# Board.net
KiCad netlist of a schematic drawn in EAGLE
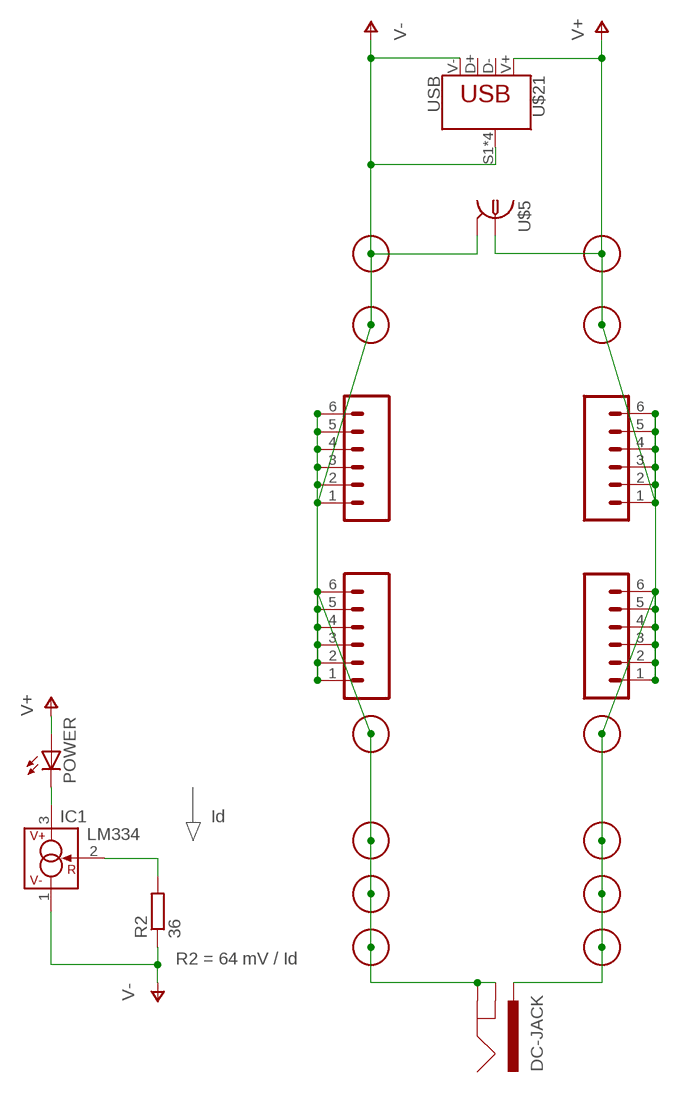
[diagram p0: schematic, sheet 1]

(export (version "E")
  (design (tool "Eeschema 10.0.6"))
  (components
    (comp (ref "IC1")
      (value "LM334")
      (footprint "eagle-import:SO08")
      (libsource (lib "eagle-import") (part "LM34SM3"))
    )
    (comp (ref "POWER")
      (value "LED5MM")
      (footprint "eagle-import:LED5MM")
      (libsource (lib "eagle-import") (part "LED5MM"))
    )
    (comp (ref "R2")
      (value "36")
      (footprint "eagle-import:R0603")
      (libsource (lib "eagle-import") (part "R-EU_R0603"))
    )
    (comp (ref "U$1")
      (value "6MM-BANANA-PLUGSCREW-BLACK")
      (footprint "eagle-import:6MM-TERMINAL-POST-BLACK")
      (libsource (lib "eagle-import") (part "6MM-BANANA-PLUGSCREW-BLACK"))
    )
    (comp (ref "U$2")
      (value "6MM-BANANA-PLUGSCREW-RED")
      (footprint "eagle-import:6MM-TERMINAL-POST-RED")
      (libsource (lib "eagle-import") (part "6MM-BANANA-PLUGSCREW-RED"))
    )
    (comp (ref "U$3")
      (value "6MM-BANANA-PLUGSCREW-BLACK")
      (footprint "eagle-import:6MM-TERMINAL-POST-BLACK")
      (libsource (lib "eagle-import") (part "6MM-BANANA-PLUGSCREW-BLACK"))
    )
    (comp (ref "U$4")
      (value "6MM-BANANA-PLUGSCREW-RED")
      (footprint "eagle-import:6MM-TERMINAL-POST-RED")
      (libsource (lib "eagle-import") (part "6MM-BANANA-PLUGSCREW-RED"))
    )
    (comp (ref "U$5")
      (value "BNC-VTE-1-1337541-0")
      (footprint "eagle-import:BNC-V")
      (libsource (lib "eagle-import") (part "BNC-VTE-1-1337541-0"))
    )
    (comp (ref "U$6")
      (value "PINHEADER-1X6MALE_LOCK")
      (footprint "eagle-import:1X06_LOCK")
      (libsource (lib "eagle-import") (part "PINHEADER-1X6MALE_LOCK"))
    )
    (comp (ref "U$7")
      (value "PINHEADER-1X6MALE_LOCK")
      (footprint "eagle-import:1X06_LOCK")
      (libsource (lib "eagle-import") (part "PINHEADER-1X6MALE_LOCK"))
    )
    (comp (ref "U$8")
      (value "PINHEADER-1X6FEMALE_LOCK")
      (footprint "eagle-import:1X06_FEMALE_LOCK.010")
      (libsource (lib "eagle-import") (part "PINHEADER-1X6FEMALE_LOCK"))
    )
    (comp (ref "U$9")
      (value "PINHEADER-1X6FEMALE_LOCK")
      (footprint "eagle-import:1X06_FEMALE_LOCK.010")
      (libsource (lib "eagle-import") (part "PINHEADER-1X6FEMALE_LOCK"))
    )
    (comp (ref "U$10")
      (value "TERMINAL-BLOCK-2")
      (footprint "eagle-import:MKDSN1,5_2-5,08")
      (libsource (lib "eagle-import") (part "TERMINAL-BLOCK-2"))
    )
    (comp (ref "U$12")
      (value "DC-JACK")
      (footprint "eagle-import:POWER_JACK_PTH")
      (libsource (lib "eagle-import") (part "DC-JACK"))
    )
    (comp (ref "U$14")
      (value "TERMINAL-1")
      (footprint "eagle-import:TE-726386")
      (libsource (lib "eagle-import") (part "TERMINAL-1"))
    )
    (comp (ref "U$15")
      (value "TERMINAL-1")
      (footprint "eagle-import:TE-726386")
      (libsource (lib "eagle-import") (part "TERMINAL-1"))
    )
    (comp (ref "U$16")
      (value "TERMINAL-1BRIDGE")
      (footprint "eagle-import:VOGT-1098A.68")
      (libsource (lib "eagle-import") (part "TERMINAL-1BRIDGE"))
    )
    (comp (ref "U$17")
      (value "TERMINAL-1BRIDGE")
      (footprint "eagle-import:VOGT-1098A.68")
      (libsource (lib "eagle-import") (part "TERMINAL-1BRIDGE"))
    )
    (comp (ref "U$18")
      (value "TERMINAL-1")
      (footprint "eagle-import:TE-726386")
      (libsource (lib "eagle-import") (part "TERMINAL-1"))
    )
    (comp (ref "U$19")
      (value "TERMINAL-1")
      (footprint "eagle-import:TE-726386")
      (libsource (lib "eagle-import") (part "TERMINAL-1"))
    )
    (comp (ref "U$21")
      (value "USB")
      (footprint "eagle-import:ECON-USBBUVA")
      (libsource (lib "eagle-import") (part "USB"))
    )
  )
  (nets
    (net (code "1") (name "Net-(IC1-R)") (class "Default")
      (node (ref "IC1") (pin "2") (pinfunction "R_2") (pintype "passive"))
      (node (ref "R2") (pin "2") (pinfunction "2_2") (pintype "passive"))
    )
    (net (code "2") (name "Net-(IC1-V+)") (class "Default")
      (node (ref "IC1") (pin "3") (pinfunction "V+_3") (pintype "passive"))
      (node (ref "POWER") (pin "K") (pinfunction "C_K") (pintype "passive"))
    )
    (net (code "3") (name "V+") (class "Default")
      (node (ref "POWER") (pin "A") (pinfunction "A_A") (pintype "passive"))
      (node (ref "U$10") (pin "1") (pinfunction "P$1_1") (pintype "bidirectional"))
      (node (ref "U$12") (pin "PWR") (pinfunction "PWR_PWR") (pintype "bidirectional"))
      (node (ref "U$15") (pin "P$1") (pinfunction "P$1_P$1") (pintype "bidirectional"))
      (node (ref "U$15") (pin "P$2") (pinfunction "P$1_P$2") (pintype "bidirectional"))
      (node (ref "U$16") (pin "P$1") (pinfunction "P$1_P$1") (pintype "bidirectional"))
      (node (ref "U$16") (pin "P$2") (pinfunction "P$1_P$2") (pintype "bidirectional"))
      (node (ref "U$19") (pin "P$1") (pinfunction "P$1_P$1") (pintype "bidirectional"))
      (node (ref "U$19") (pin "P$2") (pinfunction "P$1_P$2") (pintype "bidirectional"))
      (node (ref "U$2") (pin "P$1") (pinfunction "P$1_P$1") (pintype "bidirectional"))
      (node (ref "U$21") (pin "V+") (pinfunction "VBUS_V+") (pintype "power_in"))
      (node (ref "U$4") (pin "P$1") (pinfunction "P$1_P$1") (pintype "bidirectional"))
      (node (ref "U$5") (pin "CONDUCTOR1") (pinfunction "C_CONDUCTOR1") (pintype "passive"))
      (node (ref "U$7") (pin "1") (pinfunction "1_1") (pintype "passive"))
      (node (ref "U$7") (pin "2") (pinfunction "2_2") (pintype "passive"))
      (node (ref "U$7") (pin "3") (pinfunction "3_3") (pintype "passive"))
      (node (ref "U$7") (pin "4") (pinfunction "4_4") (pintype "passive"))
      (node (ref "U$7") (pin "5") (pinfunction "5_5") (pintype "passive"))
      (node (ref "U$7") (pin "6") (pinfunction "6_6") (pintype "passive"))
      (node (ref "U$9") (pin "1") (pinfunction "1_1") (pintype "passive"))
      (node (ref "U$9") (pin "2") (pinfunction "2_2") (pintype "passive"))
      (node (ref "U$9") (pin "3") (pinfunction "3_3") (pintype "passive"))
      (node (ref "U$9") (pin "4") (pinfunction "4_4") (pintype "passive"))
      (node (ref "U$9") (pin "5") (pinfunction "5_5") (pintype "passive"))
      (node (ref "U$9") (pin "6") (pinfunction "6_6") (pintype "passive"))
    )
    (net (code "4") (name "V-") (class "Default")
      (node (ref "IC1") (pin "1") (pinfunction "V-_1") (pintype "passive"))
      (node (ref "R2") (pin "1") (pinfunction "1_1") (pintype "passive"))
      (node (ref "U$1") (pin "P$1") (pinfunction "P$1_P$1") (pintype "bidirectional"))
      (node (ref "U$10") (pin "2") (pinfunction "P$1_2") (pintype "bidirectional"))
      (node (ref "U$12") (pin "GND") (pinfunction "GND_GND") (pintype "bidirectional"))
      (node (ref "U$12") (pin "GNDBREAK") (pinfunction "GNDBREAK_GNDBREAK") (pintype "bidirectional"))
      (node (ref "U$14") (pin "P$1") (pinfunction "P$1_P$1") (pintype "bidirectional"))
      (node (ref "U$14") (pin "P$2") (pinfunction "P$1_P$2") (pintype "bidirectional"))
      (node (ref "U$17") (pin "P$1") (pinfunction "P$1_P$1") (pintype "bidirectional"))
      (node (ref "U$17") (pin "P$2") (pinfunction "P$1_P$2") (pintype "bidirectional"))
      (node (ref "U$18") (pin "P$1") (pinfunction "P$1_P$1") (pintype "bidirectional"))
      (node (ref "U$18") (pin "P$2") (pinfunction "P$1_P$2") (pintype "bidirectional"))
      (node (ref "U$21") (pin "S1") (pinfunction "SHIELD_S1") (pintype "bidirectional"))
      (node (ref "U$21") (pin "S2") (pinfunction "SHIELD_S2") (pintype "bidirectional"))
      (node (ref "U$21") (pin "S3") (pinfunction "SHIELD_S3") (pintype "bidirectional"))
      (node (ref "U$21") (pin "S4") (pinfunction "SHIELD_S4") (pintype "bidirectional"))
      (node (ref "U$21") (pin "V-") (pinfunction "GND_V-") (pintype "power_in"))
      (node (ref "U$3") (pin "P$1") (pinfunction "P$1_P$1") (pintype "bidirectional"))
      (node (ref "U$5") (pin "CONDUCTOR2") (pinfunction "S_CONDUCTOR2") (pintype "passive"))
      (node (ref "U$5") (pin "SHIELD1") (pinfunction "S_SHIELD1") (pintype "passive"))
      (node (ref "U$5") (pin "SHIELD2") (pinfunction "S_SHIELD2") (pintype "passive"))
      (node (ref "U$6") (pin "1") (pinfunction "1_1") (pintype "passive"))
      (node (ref "U$6") (pin "2") (pinfunction "2_2") (pintype "passive"))
      (node (ref "U$6") (pin "3") (pinfunction "3_3") (pintype "passive"))
      (node (ref "U$6") (pin "4") (pinfunction "4_4") (pintype "passive"))
      (node (ref "U$6") (pin "5") (pinfunction "5_5") (pintype "passive"))
      (node (ref "U$6") (pin "6") (pinfunction "6_6") (pintype "passive"))
      (node (ref "U$8") (pin "1") (pinfunction "1_1") (pintype "passive"))
      (node (ref "U$8") (pin "2") (pinfunction "2_2") (pintype "passive"))
      (node (ref "U$8") (pin "3") (pinfunction "3_3") (pintype "passive"))
      (node (ref "U$8") (pin "4") (pinfunction "4_4") (pintype "passive"))
      (node (ref "U$8") (pin "5") (pinfunction "5_5") (pintype "passive"))
      (node (ref "U$8") (pin "6") (pinfunction "6_6") (pintype "passive"))
    )
    (net (code "5") (name "unconnected-(U$21-PadD+)") (class "Default")
      (node (ref "U$21") (pin "D+") (pinfunction "D+_D+") (pintype "bidirectional"))
    )
    (net (code "6") (name "unconnected-(U$21-PadD-)") (class "Default")
      (node (ref "U$21") (pin "D-") (pinfunction "D-_D-") (pintype "bidirectional"))
    )
  )
)
